# Camera_MCU.net
KiCad netlist of a schematic drawn in Altium Designer
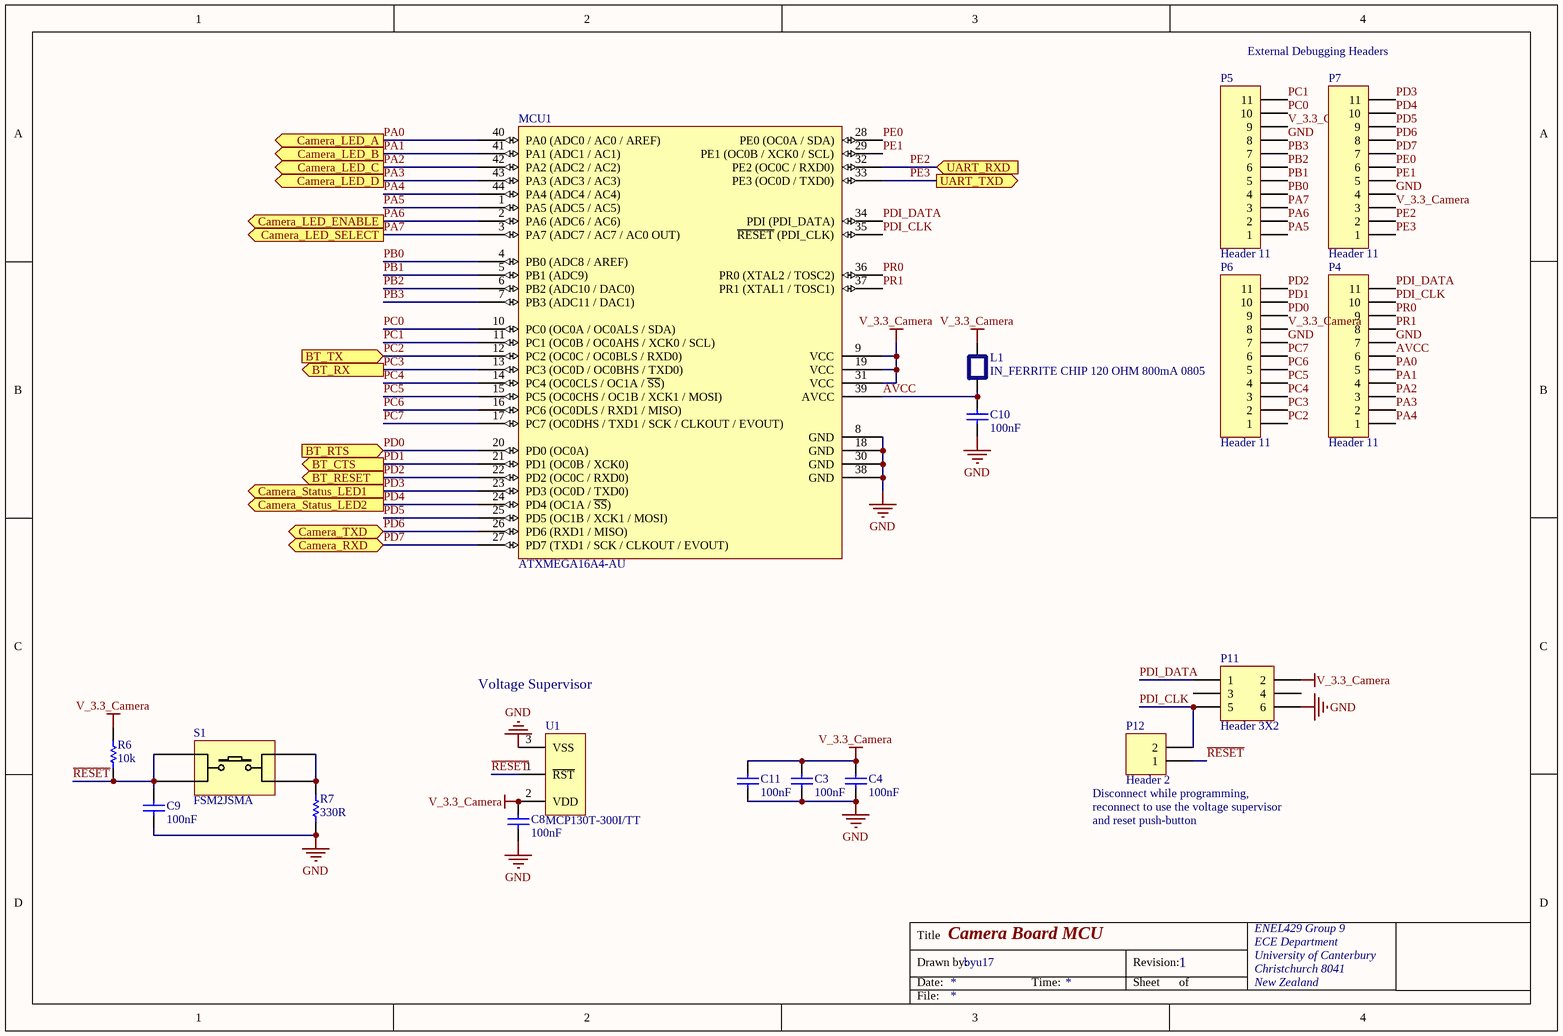
[diagram p0: Camera_MCU.SchDoc]

(export (version "E")
  (design (tool "Eeschema 10.0.6"))
  (components
    (comp (ref "C3")
      (value "100nF")
      (footprint "0603")
      (description "CAP CER .10UF 50V X5R 0603")
      (fields (field (name "PART NUMBER") "CP_100nF 0603") (field (name "MANUFACTURER") "Taiyo Yuden"))
      (libsource (lib "ENEL429_4") (part "CP_100nF 0603"))
    )
    (comp (ref "C4")
      (value "100nF")
      (footprint "0603")
      (description "CAP CER .10UF 50V X5R 0603")
      (fields (field (name "PART NUMBER") "CP_100nF 0603") (field (name "MANUFACTURER") "Taiyo Yuden"))
      (libsource (lib "ENEL429_4") (part "CP_100nF 0603"))
    )
    (comp (ref "C8")
      (value "100nF")
      (footprint "0603")
      (description "CAP CER .10UF 50V X5R 0603")
      (fields (field (name "PART NUMBER") "CP_100nF 0603") (field (name "MANUFACTURER") "Taiyo Yuden"))
      (libsource (lib "ENEL429_4") (part "CP_100nF 0603"))
    )
    (comp (ref "C9")
      (value "100nF")
      (footprint "0603")
      (description "CAP CER .10UF 50V X5R 0603")
      (fields (field (name "PART NUMBER") "CP_100nF 0603") (field (name "MANUFACTURER") "Taiyo Yuden"))
      (libsource (lib "ENEL429_4") (part "CP_100nF 0603"))
    )
    (comp (ref "C10")
      (value "100nF")
      (footprint "0603")
      (description "CAP CER .10UF 50V X5R 0603")
      (fields (field (name "PART NUMBER") "CP_100nF 0603") (field (name "MANUFACTURER") "Taiyo Yuden"))
      (libsource (lib "ENEL429_4") (part "CP_100nF 0603"))
    )
    (comp (ref "C11")
      (value "100nF")
      (footprint "0603")
      (description "CAP CER .10UF 50V X5R 0603")
      (fields (field (name "PART NUMBER") "CP_100nF 0603") (field (name "MANUFACTURER") "Taiyo Yuden"))
      (libsource (lib "ENEL429_4") (part "CP_100nF 0603"))
    )
    (comp (ref "L1")
      (value "IN_FERRITE CHIP 120 OHM 800mA 0805")
      (footprint "0805")
      (description "FERRITE CHIP 120 OHM 800mA 0805")
      (fields (field (name "MANUFACTURER") "TDK"))
      (libsource (lib "ENEL429_4") (part "IN_FERRITE CHIP 120 OHM 800mA 0805"))
    )
    (comp (ref "MCU1")
      (value "ATXMEGA16A4-AU")
      (footprint "TQFP80P1200X1200X120-44N")
      (fields (field (name "MANUFACTURER") "ATMEL"))
      (libsource (lib "Wacky_1") (part "ATXMEGA16A4-AU"))
    )
    (comp (ref "P4")
      (value "Header 11")
      (footprint "HDR1X11")
      (description "Header, 11-Pin")
      (fields (field (name "PUBLISHER") "Altium Limited"))
      (libsource (lib "Miscellaneous Connectors") (part "Header 11"))
    )
    (comp (ref "P5")
      (value "Header 11")
      (footprint "HDR1X11")
      (description "Header, 11-Pin")
      (fields (field (name "PUBLISHER") "Altium Limited"))
      (libsource (lib "Miscellaneous Connectors") (part "Header 11"))
    )
    (comp (ref "P6")
      (value "Header 11")
      (footprint "HDR1X11")
      (description "Header, 11-Pin")
      (fields (field (name "PUBLISHER") "Altium Limited"))
      (libsource (lib "Miscellaneous Connectors") (part "Header 11"))
    )
    (comp (ref "P7")
      (value "Header 11")
      (footprint "HDR1X11")
      (description "Header, 11-Pin")
      (fields (field (name "PUBLISHER") "Altium Limited"))
      (libsource (lib "Miscellaneous Connectors") (part "Header 11"))
    )
    (comp (ref "P11")
      (value "Header 3X2")
      (footprint "HDR2X3")
      (description "Header, 3-Pin, Dual row")
      (fields (field (name "PUBLISHER") "Altium Limited"))
      (libsource (lib "Miscellaneous Connectors") (part "Header 3X2"))
    )
    (comp (ref "P12")
      (value "Header 2")
      (footprint "HDR1X2")
      (description "Header, 2-Pin")
      (fields (field (name "PUBLISHER") "Altium Limited"))
      (libsource (lib "Miscellaneous Connectors") (part "Header 2"))
    )
    (comp (ref "R6")
      (value "10k")
      (footprint "0603")
      (description "RES 10.0K OHM 1/10W 1% 0603 SMD")
      (fields (field (name "PART NUMBER") "RS_10k 0603") (field (name "MANUFACTURER") "Yageo"))
      (libsource (lib "ENEL429_4") (part "RS_10k 0603"))
    )
    (comp (ref "R7")
      (value "330R")
      (footprint "0603")
      (description "RES 330 OHM 1/10W 1% 0603 SMD")
      (fields (field (name "PART NUMBER") "RS_330R 0603") (field (name "MANUFACTURER") "Yageo"))
      (libsource (lib "ENEL429_4") (part "RS_330R 0603"))
    )
    (comp (ref "S1")
      (value "FSM2JSMA")
      (footprint "FSM2JSMA")
      (description "DPST SMD Switch")
      (fields (field (name "MANUFACTURER") "Tyco Electronics") (field (name "PART NUMBER") "SW_FSM2JSMA"))
      (libsource (lib "ENEL429_4") (part "SW_FSM2JSMA"))
    )
    (comp (ref "U1")
      (value "MCP130T-300I/TT")
      (footprint "SOT-23-TT3_N")
      (fields (field (name "PUBLISHER") "Altium Limited"))
      (libsource (lib "Microchip Power Mgt CPU-System Supervisor") (part "MCP130T-300I/TT"))
    )
  )
  (nets
    (net (code "1") (name "/AVCC") (class "Default")
      (node (ref "C10") (pin "2") (pinfunction "2_2") (pintype "passive"))
      (node (ref "L1") (pin "2") (pinfunction "1_2") (pintype "power_in"))
      (node (ref "MCU1") (pin "39") (pinfunction "AVCC_39") (pintype "passive"))
      (node (ref "P4") (pin "6") (pinfunction "6_6") (pintype "passive"))
    )
    (net (code "2") (name "/PA0") (class "Default")
      (node (ref "MCU1") (pin "40") (pinfunction "PA0_(ADC0_/_AC0_/_AREF)_40") (pintype "bidirectional"))
      (node (ref "P4") (pin "5") (pinfunction "5_5") (pintype "passive"))
    )
    (net (code "3") (name "/PA1") (class "Default")
      (node (ref "MCU1") (pin "41") (pinfunction "PA1_(ADC1_/_AC1)_41") (pintype "bidirectional"))
      (node (ref "P4") (pin "4") (pinfunction "4_4") (pintype "passive"))
    )
    (net (code "4") (name "/PA2") (class "Default")
      (node (ref "MCU1") (pin "42") (pinfunction "PA2_(ADC2_/_AC2)_42") (pintype "bidirectional"))
      (node (ref "P4") (pin "3") (pinfunction "3_3") (pintype "passive"))
    )
    (net (code "5") (name "/PA3") (class "Default")
      (node (ref "MCU1") (pin "43") (pinfunction "PA3_(ADC3_/_AC3)_43") (pintype "bidirectional"))
      (node (ref "P4") (pin "2") (pinfunction "2_2") (pintype "passive"))
    )
    (net (code "6") (name "/PA4") (class "Default")
      (node (ref "MCU1") (pin "44") (pinfunction "PA4_(ADC4_/_AC4)_44") (pintype "bidirectional"))
      (node (ref "P4") (pin "1") (pinfunction "1_1") (pintype "passive"))
    )
    (net (code "7") (name "/PA5") (class "Default")
      (node (ref "MCU1") (pin "1") (pinfunction "PA5_(ADC5_/_AC5)_1") (pintype "bidirectional"))
      (node (ref "P5") (pin "1") (pinfunction "1_1") (pintype "passive"))
    )
    (net (code "8") (name "/PA6") (class "Default")
      (node (ref "MCU1") (pin "2") (pinfunction "PA6_(ADC6_/_AC6)_2") (pintype "bidirectional"))
      (node (ref "P5") (pin "2") (pinfunction "2_2") (pintype "passive"))
    )
    (net (code "9") (name "/PA7") (class "Default")
      (node (ref "MCU1") (pin "3") (pinfunction "PA7_(ADC7_/_AC7_/_AC0_OUT)_3") (pintype "bidirectional"))
      (node (ref "P5") (pin "3") (pinfunction "3_3") (pintype "passive"))
    )
    (net (code "10") (name "/PB0") (class "Default")
      (node (ref "MCU1") (pin "4") (pinfunction "PB0_(ADC8_/_AREF)_4") (pintype "bidirectional"))
      (node (ref "P5") (pin "4") (pinfunction "4_4") (pintype "passive"))
    )
    (net (code "11") (name "/PB1") (class "Default")
      (node (ref "MCU1") (pin "5") (pinfunction "PB1_(ADC9)_5") (pintype "bidirectional"))
      (node (ref "P5") (pin "5") (pinfunction "5_5") (pintype "passive"))
    )
    (net (code "12") (name "/PB2") (class "Default")
      (node (ref "MCU1") (pin "6") (pinfunction "PB2_(ADC10_/_DAC0)_6") (pintype "bidirectional"))
      (node (ref "P5") (pin "6") (pinfunction "6_6") (pintype "passive"))
    )
    (net (code "13") (name "/PB3") (class "Default")
      (node (ref "MCU1") (pin "7") (pinfunction "PB3_(ADC11_/_DAC1)_7") (pintype "bidirectional"))
      (node (ref "P5") (pin "7") (pinfunction "7_7") (pintype "passive"))
    )
    (net (code "14") (name "/PC0") (class "Default")
      (node (ref "MCU1") (pin "10") (pinfunction "PC0_(OC0A_/_OC0ALS_/_SDA)_10") (pintype "bidirectional"))
      (node (ref "P5") (pin "10") (pinfunction "10_10") (pintype "passive"))
    )
    (net (code "15") (name "/PC1") (class "Default")
      (node (ref "MCU1") (pin "11") (pinfunction "PC1_(OC0B_/_OC0AHS_/_XCK0_/_SCL)_11") (pintype "bidirectional"))
      (node (ref "P5") (pin "11") (pinfunction "11_11") (pintype "passive"))
    )
    (net (code "16") (name "/PC2") (class "Default")
      (node (ref "MCU1") (pin "12") (pinfunction "PC2_(OC0C_/_OC0BLS_/_RXD0)_12") (pintype "bidirectional"))
      (node (ref "P6") (pin "1") (pinfunction "1_1") (pintype "passive"))
    )
    (net (code "17") (name "/PC3") (class "Default")
      (node (ref "MCU1") (pin "13") (pinfunction "PC3_(OC0D_/_OC0BHS_/_TXD0)_13") (pintype "bidirectional"))
      (node (ref "P6") (pin "2") (pinfunction "2_2") (pintype "passive"))
    )
    (net (code "18") (name "/PC4") (class "Default")
      (node (ref "MCU1") (pin "14") (pinfunction "PC4_(OC0CLS_/_OC1A_/_~{SS})_14") (pintype "bidirectional"))
      (node (ref "P6") (pin "3") (pinfunction "3_3") (pintype "passive"))
    )
    (net (code "19") (name "/PC5") (class "Default")
      (node (ref "MCU1") (pin "15") (pinfunction "PC5_(OC0CHS_/_OC1B_/_XCK1_/_MOSI)_15") (pintype "bidirectional"))
      (node (ref "P6") (pin "4") (pinfunction "4_4") (pintype "passive"))
    )
    (net (code "20") (name "/PC6") (class "Default")
      (node (ref "MCU1") (pin "16") (pinfunction "PC6_(OC0DLS_/_RXD1_/_MISO)_16") (pintype "bidirectional"))
      (node (ref "P6") (pin "5") (pinfunction "5_5") (pintype "passive"))
    )
    (net (code "21") (name "/PC7") (class "Default")
      (node (ref "MCU1") (pin "17") (pinfunction "PC7_(OC0DHS_/_TXD1_/_SCK_/_CLKOUT_/_EVOUT)_17") (pintype "bidirectional"))
      (node (ref "P6") (pin "6") (pinfunction "6_6") (pintype "passive"))
    )
    (net (code "22") (name "/PD0") (class "Default")
      (node (ref "MCU1") (pin "20") (pinfunction "PD0_(OC0A)_20") (pintype "bidirectional"))
      (node (ref "P6") (pin "9") (pinfunction "9_9") (pintype "passive"))
    )
    (net (code "23") (name "/PD1") (class "Default")
      (node (ref "MCU1") (pin "21") (pinfunction "PD1_(OC0B_/_XCK0)_21") (pintype "bidirectional"))
      (node (ref "P6") (pin "10") (pinfunction "10_10") (pintype "passive"))
    )
    (net (code "24") (name "/PD2") (class "Default")
      (node (ref "MCU1") (pin "22") (pinfunction "PD2_(OC0C_/_RXD0)_22") (pintype "bidirectional"))
      (node (ref "P6") (pin "11") (pinfunction "11_11") (pintype "passive"))
    )
    (net (code "25") (name "/PD3") (class "Default")
      (node (ref "MCU1") (pin "23") (pinfunction "PD3_(OC0D_/_TXD0)_23") (pintype "bidirectional"))
      (node (ref "P7") (pin "11") (pinfunction "11_11") (pintype "passive"))
    )
    (net (code "26") (name "/PD4") (class "Default")
      (node (ref "MCU1") (pin "24") (pinfunction "PD4_(OC1A_/_~{SS})_24") (pintype "bidirectional"))
      (node (ref "P7") (pin "10") (pinfunction "10_10") (pintype "passive"))
    )
    (net (code "27") (name "/PD5") (class "Default")
      (node (ref "MCU1") (pin "25") (pinfunction "PD5_(OC1B_/_XCK1_/_MOSI)_25") (pintype "bidirectional"))
      (node (ref "P7") (pin "9") (pinfunction "9_9") (pintype "passive"))
    )
    (net (code "28") (name "/PD6") (class "Default")
      (node (ref "MCU1") (pin "26") (pinfunction "PD6_(RXD1_/_MISO)_26") (pintype "bidirectional"))
      (node (ref "P7") (pin "8") (pinfunction "8_8") (pintype "passive"))
    )
    (net (code "29") (name "/PD7") (class "Default")
      (node (ref "MCU1") (pin "27") (pinfunction "PD7_(TXD1_/_SCK_/_CLKOUT_/_EVOUT)_27") (pintype "bidirectional"))
      (node (ref "P7") (pin "7") (pinfunction "7_7") (pintype "passive"))
    )
    (net (code "30") (name "/PDI_CLK") (class "Default")
      (node (ref "MCU1") (pin "35") (pinfunction "~{RESET}_(PDI_CLK)_35") (pintype "bidirectional"))
      (node (ref "P11") (pin "5") (pinfunction "5_5") (pintype "passive"))
      (node (ref "P12") (pin "2") (pinfunction "2_2") (pintype "passive"))
      (node (ref "P4") (pin "10") (pinfunction "10_10") (pintype "passive"))
    )
    (net (code "31") (name "/PDI_DATA") (class "Default")
      (node (ref "MCU1") (pin "34") (pinfunction "PDI_(PDI_DATA)_34") (pintype "bidirectional"))
      (node (ref "P11") (pin "1") (pinfunction "1_1") (pintype "passive"))
      (node (ref "P4") (pin "11") (pinfunction "11_11") (pintype "passive"))
    )
    (net (code "32") (name "/PE0") (class "Default")
      (node (ref "MCU1") (pin "28") (pinfunction "PE0_(OC0A_/_SDA)_28") (pintype "bidirectional"))
      (node (ref "P7") (pin "6") (pinfunction "6_6") (pintype "passive"))
    )
    (net (code "33") (name "/PE1") (class "Default")
      (node (ref "MCU1") (pin "29") (pinfunction "PE1_(OC0B_/_XCK0_/_SCL)_29") (pintype "bidirectional"))
      (node (ref "P7") (pin "5") (pinfunction "5_5") (pintype "passive"))
    )
    (net (code "34") (name "/PE2") (class "Default")
      (node (ref "MCU1") (pin "32") (pinfunction "PE2_(OC0C_/_RXD0)_32") (pintype "bidirectional"))
      (node (ref "P7") (pin "2") (pinfunction "2_2") (pintype "passive"))
    )
    (net (code "35") (name "/PE3") (class "Default")
      (node (ref "MCU1") (pin "33") (pinfunction "PE3_(OC0D_/_TXD0)_33") (pintype "bidirectional"))
      (node (ref "P7") (pin "1") (pinfunction "1_1") (pintype "passive"))
    )
    (net (code "36") (name "/PR0") (class "Default")
      (node (ref "MCU1") (pin "36") (pinfunction "PR0_(XTAL2_/_TOSC2)_36") (pintype "bidirectional"))
      (node (ref "P4") (pin "9") (pinfunction "9_9") (pintype "passive"))
    )
    (net (code "37") (name "/PR1") (class "Default")
      (node (ref "MCU1") (pin "37") (pinfunction "PR1_(XTAL1_/_TOSC1)_37") (pintype "bidirectional"))
      (node (ref "P4") (pin "8") (pinfunction "8_8") (pintype "passive"))
    )
    (net (code "38") (name "/~{RESET}") (class "Default")
      (node (ref "C9") (pin "1") (pinfunction "1_1") (pintype "passive"))
      (node (ref "P12") (pin "1") (pinfunction "1_1") (pintype "passive"))
      (node (ref "R6") (pin "1") (pinfunction "1_1") (pintype "passive"))
      (node (ref "S1") (pin "1") (pinfunction "1_1") (pintype "passive"))
      (node (ref "S1") (pin "2") (pinfunction "2_2") (pintype "passive"))
      (node (ref "U1") (pin "1") (pinfunction "~{RST}_1") (pintype "open_collector"))
    )
    (net (code "39") (name "GND") (class "Default")
      (node (ref "C10") (pin "1") (pinfunction "1_1") (pintype "passive"))
      (node (ref "C11") (pin "2") (pinfunction "2_2") (pintype "passive"))
      (node (ref "C3") (pin "1") (pinfunction "1_1") (pintype "passive"))
      (node (ref "C4") (pin "1") (pinfunction "1_1") (pintype "passive"))
      (node (ref "C8") (pin "2") (pinfunction "2_2") (pintype "passive"))
      (node (ref "C9") (pin "2") (pinfunction "2_2") (pintype "passive"))
      (node (ref "MCU1") (pin "18") (pinfunction "GND_18") (pintype "passive"))
      (node (ref "MCU1") (pin "30") (pinfunction "GND_30") (pintype "passive"))
      (node (ref "MCU1") (pin "38") (pinfunction "GND_38") (pintype "passive"))
      (node (ref "MCU1") (pin "8") (pinfunction "GND_8") (pintype "passive"))
      (node (ref "P11") (pin "6") (pinfunction "6_6") (pintype "passive"))
      (node (ref "P4") (pin "7") (pinfunction "7_7") (pintype "passive"))
      (node (ref "P5") (pin "8") (pinfunction "8_8") (pintype "passive"))
      (node (ref "P6") (pin "7") (pinfunction "7_7") (pintype "passive"))
      (node (ref "P7") (pin "4") (pinfunction "4_4") (pintype "passive"))
      (node (ref "R7") (pin "1") (pinfunction "1_1") (pintype "passive"))
      (node (ref "U1") (pin "3") (pinfunction "VSS_3") (pintype "power_in"))
    )
    (net (code "40") (name "Net-(R7-Pad2)") (class "Default")
      (node (ref "R7") (pin "2") (pinfunction "2_2") (pintype "passive"))
      (node (ref "S1") (pin "3") (pinfunction "3_3") (pintype "passive"))
      (node (ref "S1") (pin "4") (pinfunction "4_4") (pintype "passive"))
    )
    (net (code "41") (name "V_3.3_Camera") (class "Default")
      (node (ref "C11") (pin "1") (pinfunction "1_1") (pintype "passive"))
      (node (ref "C3") (pin "2") (pinfunction "2_2") (pintype "passive"))
      (node (ref "C4") (pin "2") (pinfunction "2_2") (pintype "passive"))
      (node (ref "C8") (pin "1") (pinfunction "1_1") (pintype "passive"))
      (node (ref "L1") (pin "1") (pinfunction "0_1") (pintype "power_in"))
      (node (ref "MCU1") (pin "19") (pinfunction "VCC_19") (pintype "passive"))
      (node (ref "MCU1") (pin "31") (pinfunction "VCC_31") (pintype "passive"))
      (node (ref "MCU1") (pin "9") (pinfunction "VCC_9") (pintype "passive"))
      (node (ref "P11") (pin "2") (pinfunction "2_2") (pintype "passive"))
      (node (ref "P5") (pin "9") (pinfunction "9_9") (pintype "passive"))
      (node (ref "P6") (pin "8") (pinfunction "8_8") (pintype "passive"))
      (node (ref "P7") (pin "3") (pinfunction "3_3") (pintype "passive"))
      (node (ref "R6") (pin "2") (pinfunction "2_2") (pintype "passive"))
      (node (ref "U1") (pin "2") (pinfunction "VDD_2") (pintype "power_in"))
    )
    (net (code "42") (name "unconnected-(P11-Pad3)") (class "Default")
      (node (ref "P11") (pin "3") (pinfunction "3_3") (pintype "passive"))
    )
    (net (code "43") (name "unconnected-(P11-Pad4)") (class "Default")
      (node (ref "P11") (pin "4") (pinfunction "4_4") (pintype "passive"))
    )
  )
)
